# iot1.net
KiCad netlist of a schematic drawn in EAGLE
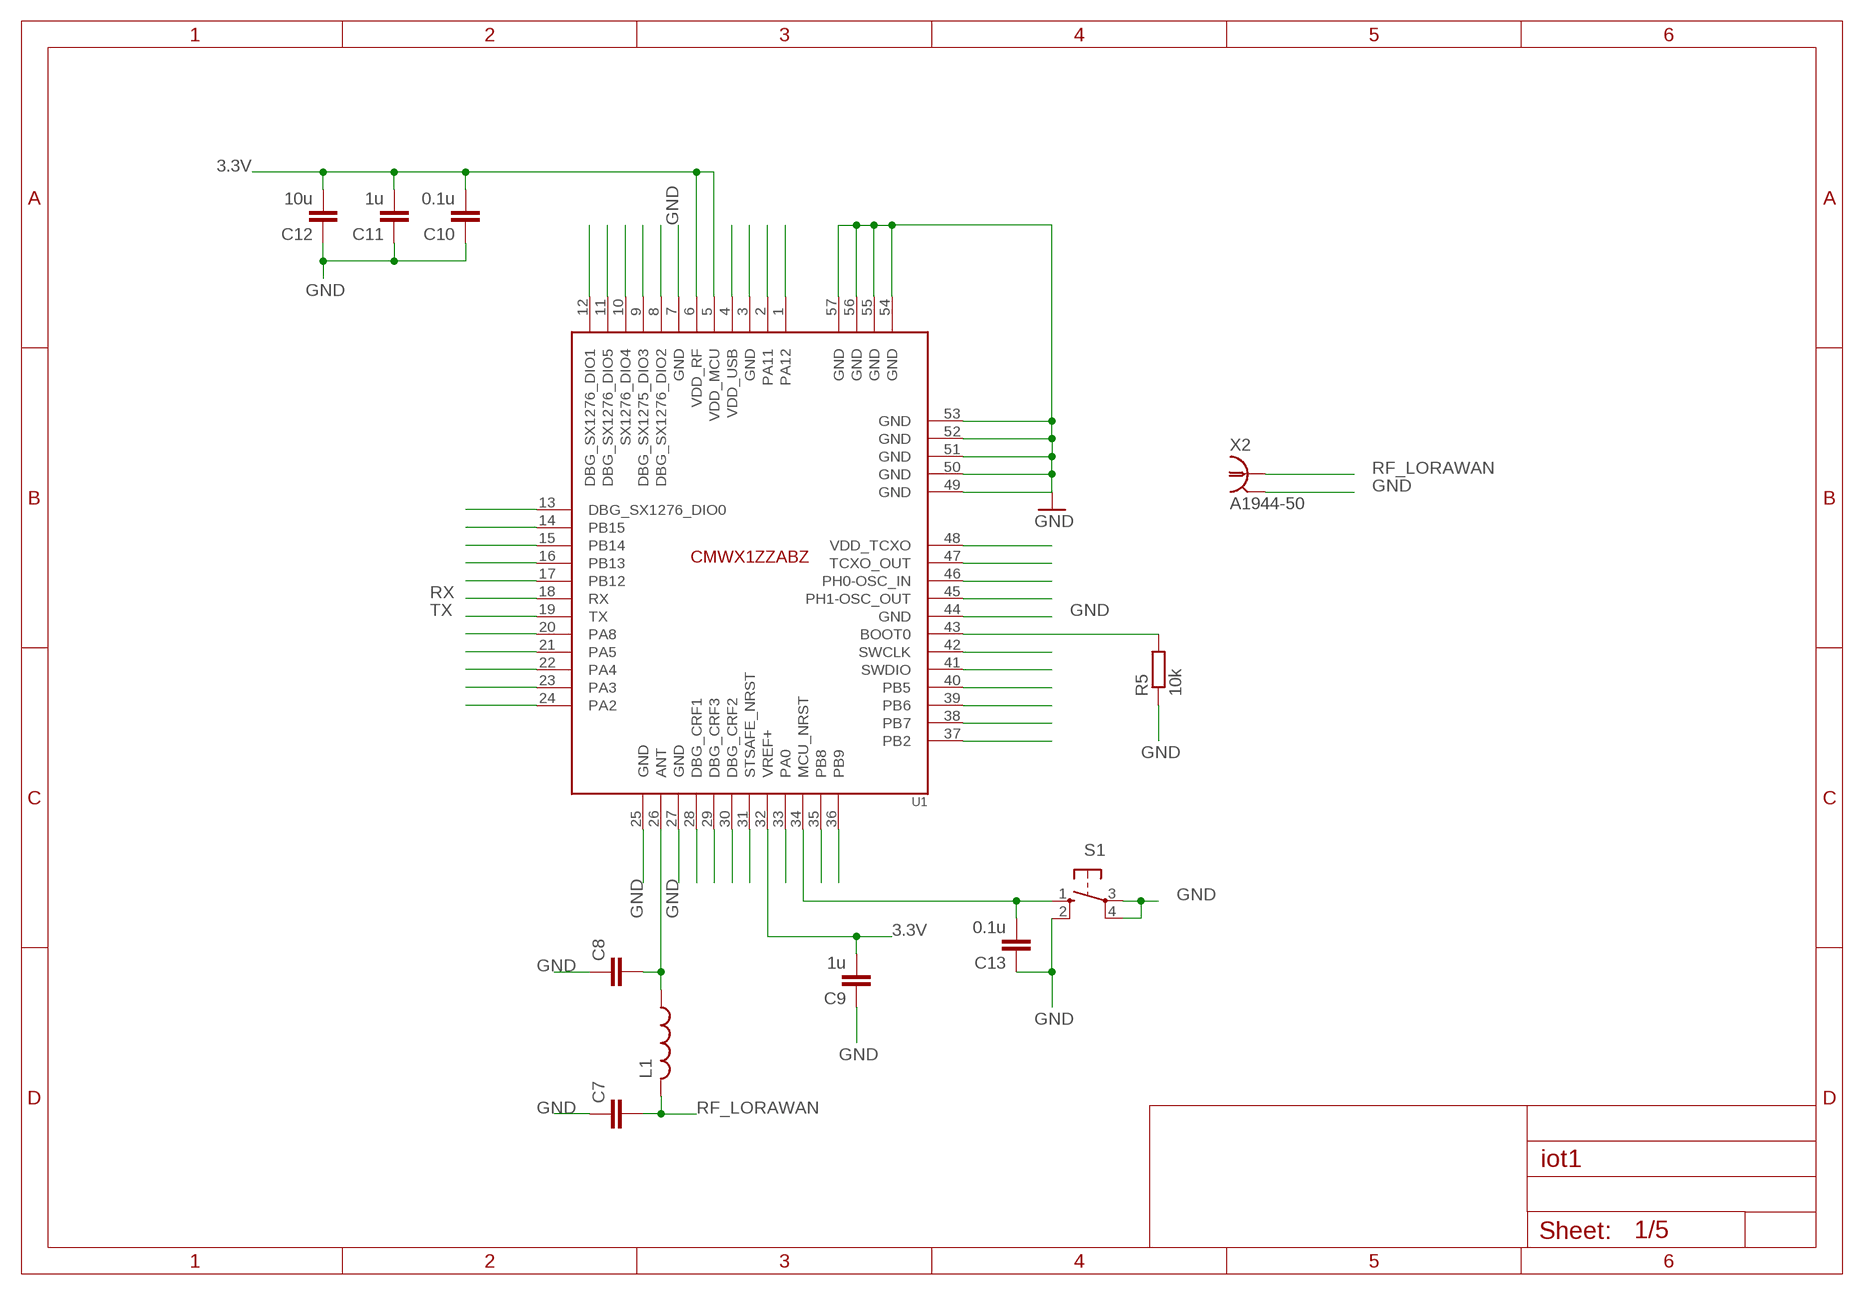
[diagram p0: schematic, sheet 1]
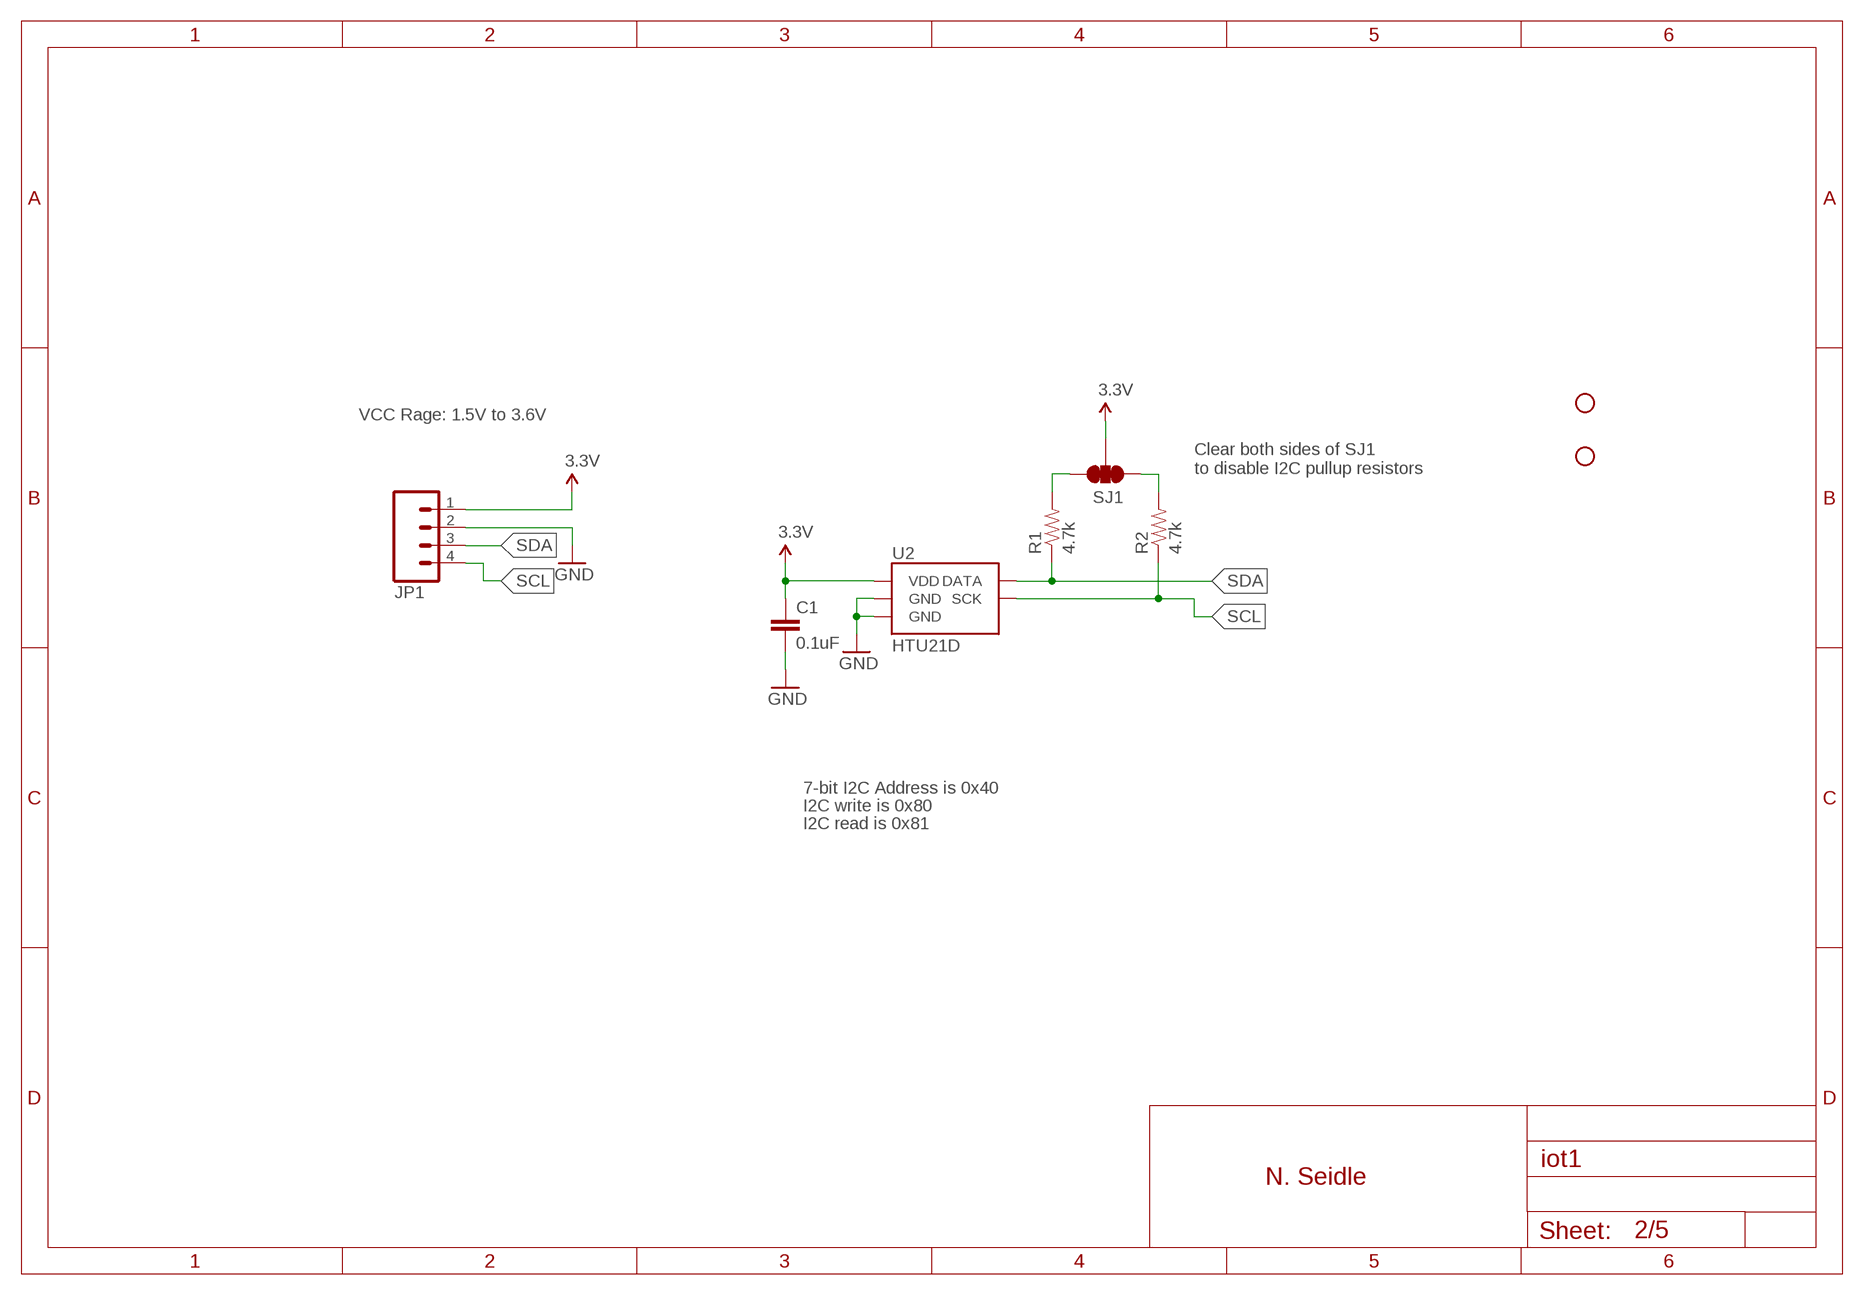
[diagram p1: schematic, sheet 2]
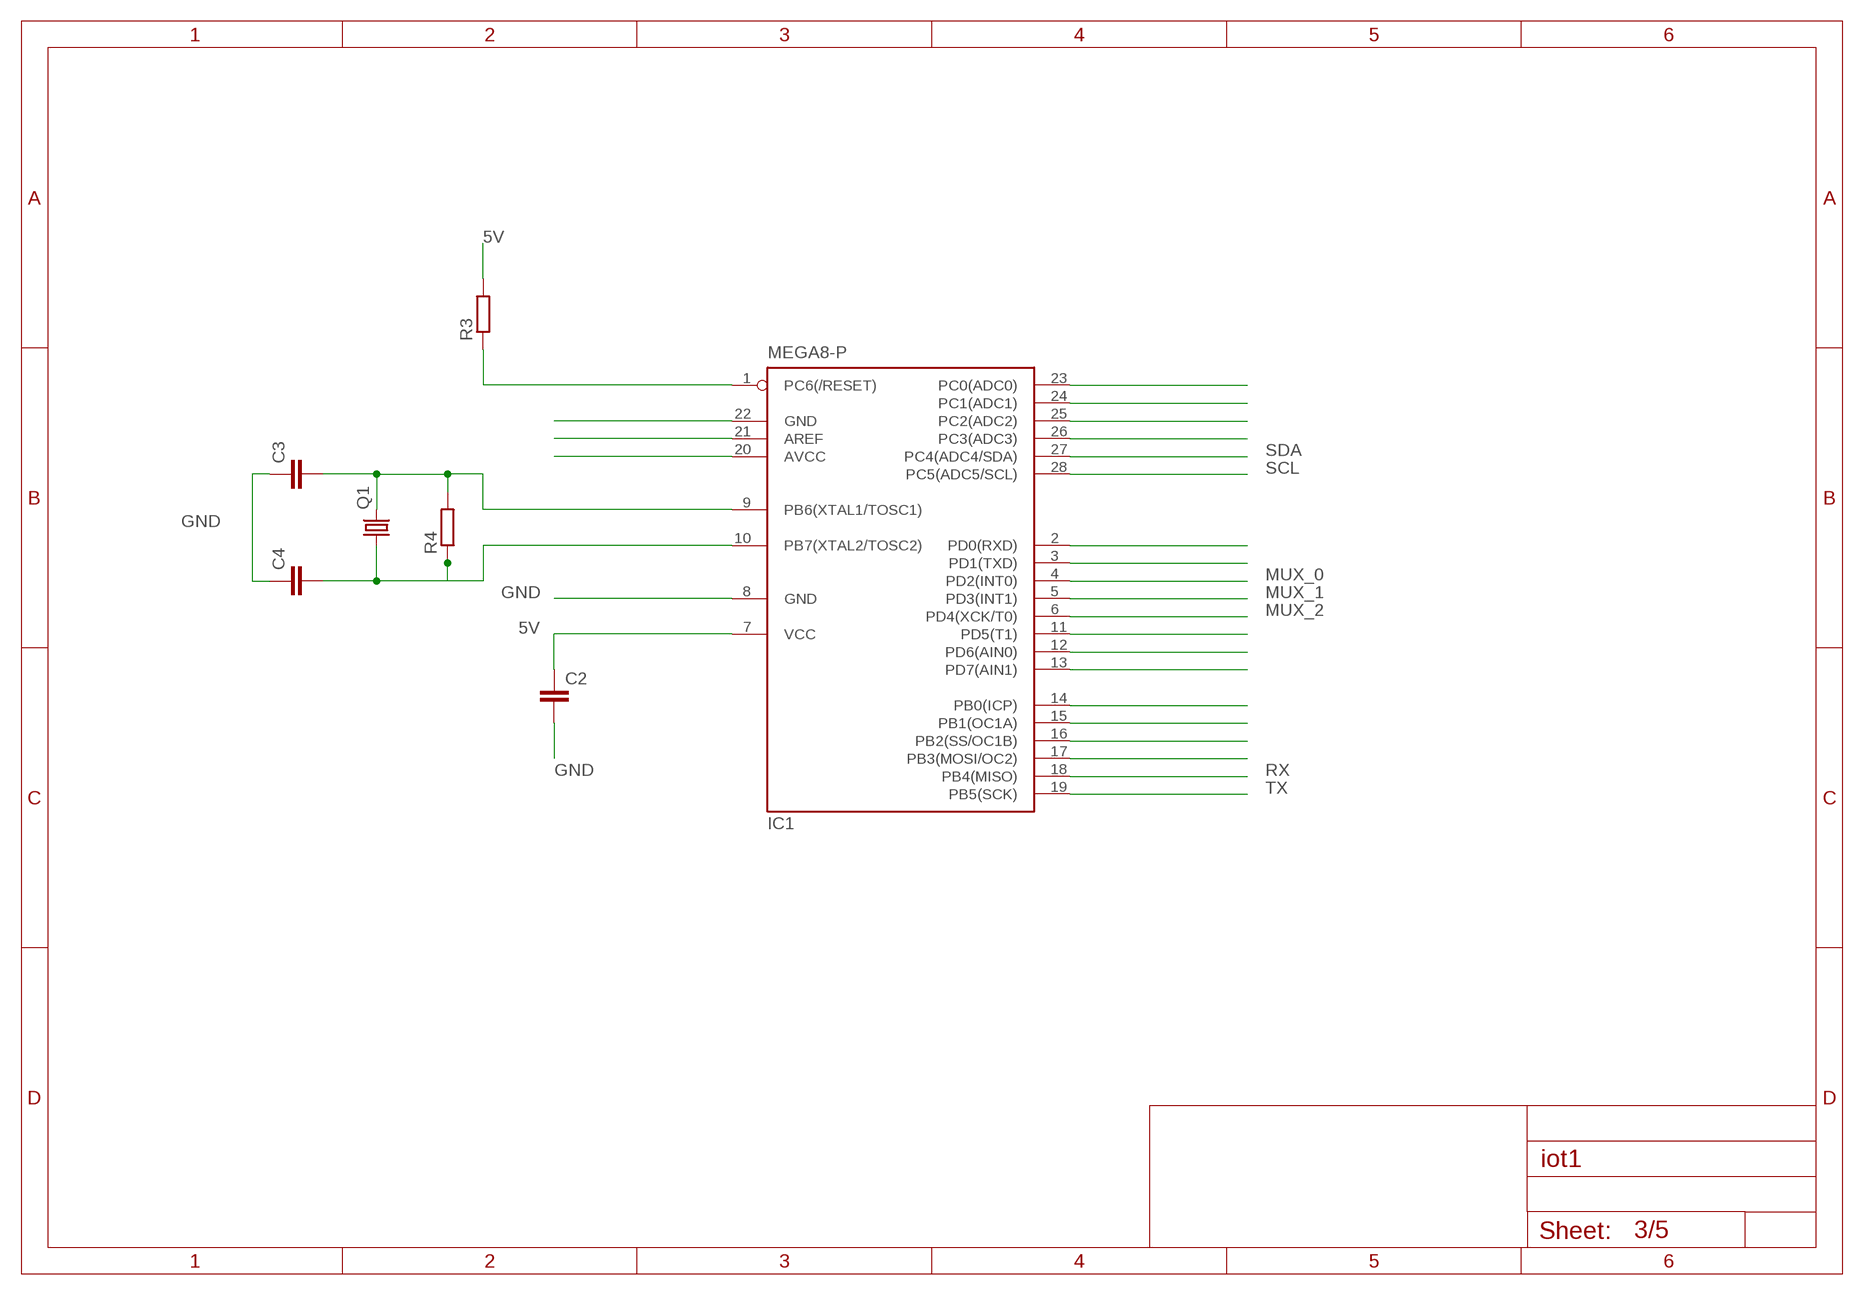
[diagram p2: schematic, sheet 3]
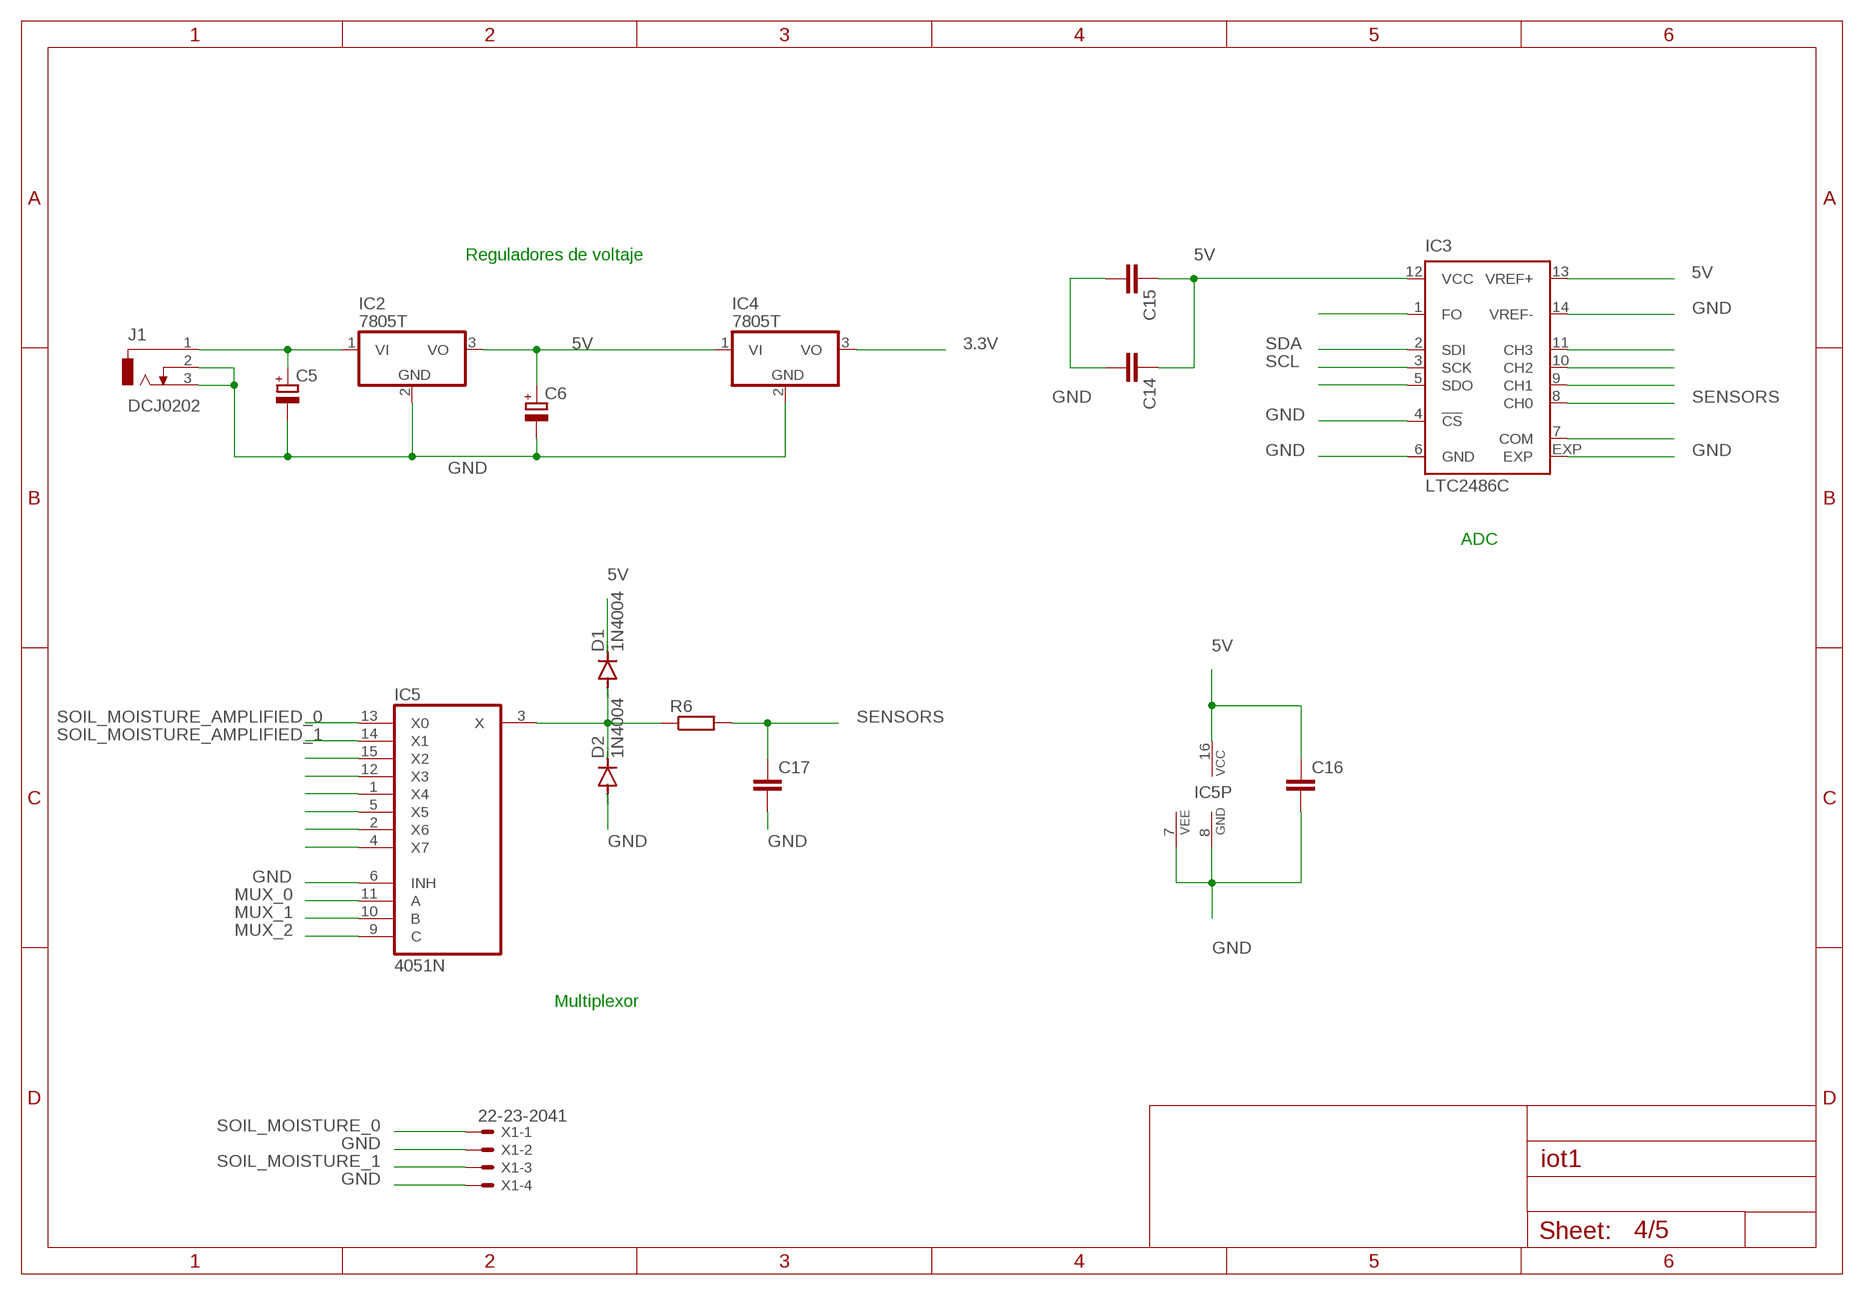
[diagram p3: schematic, sheet 4]
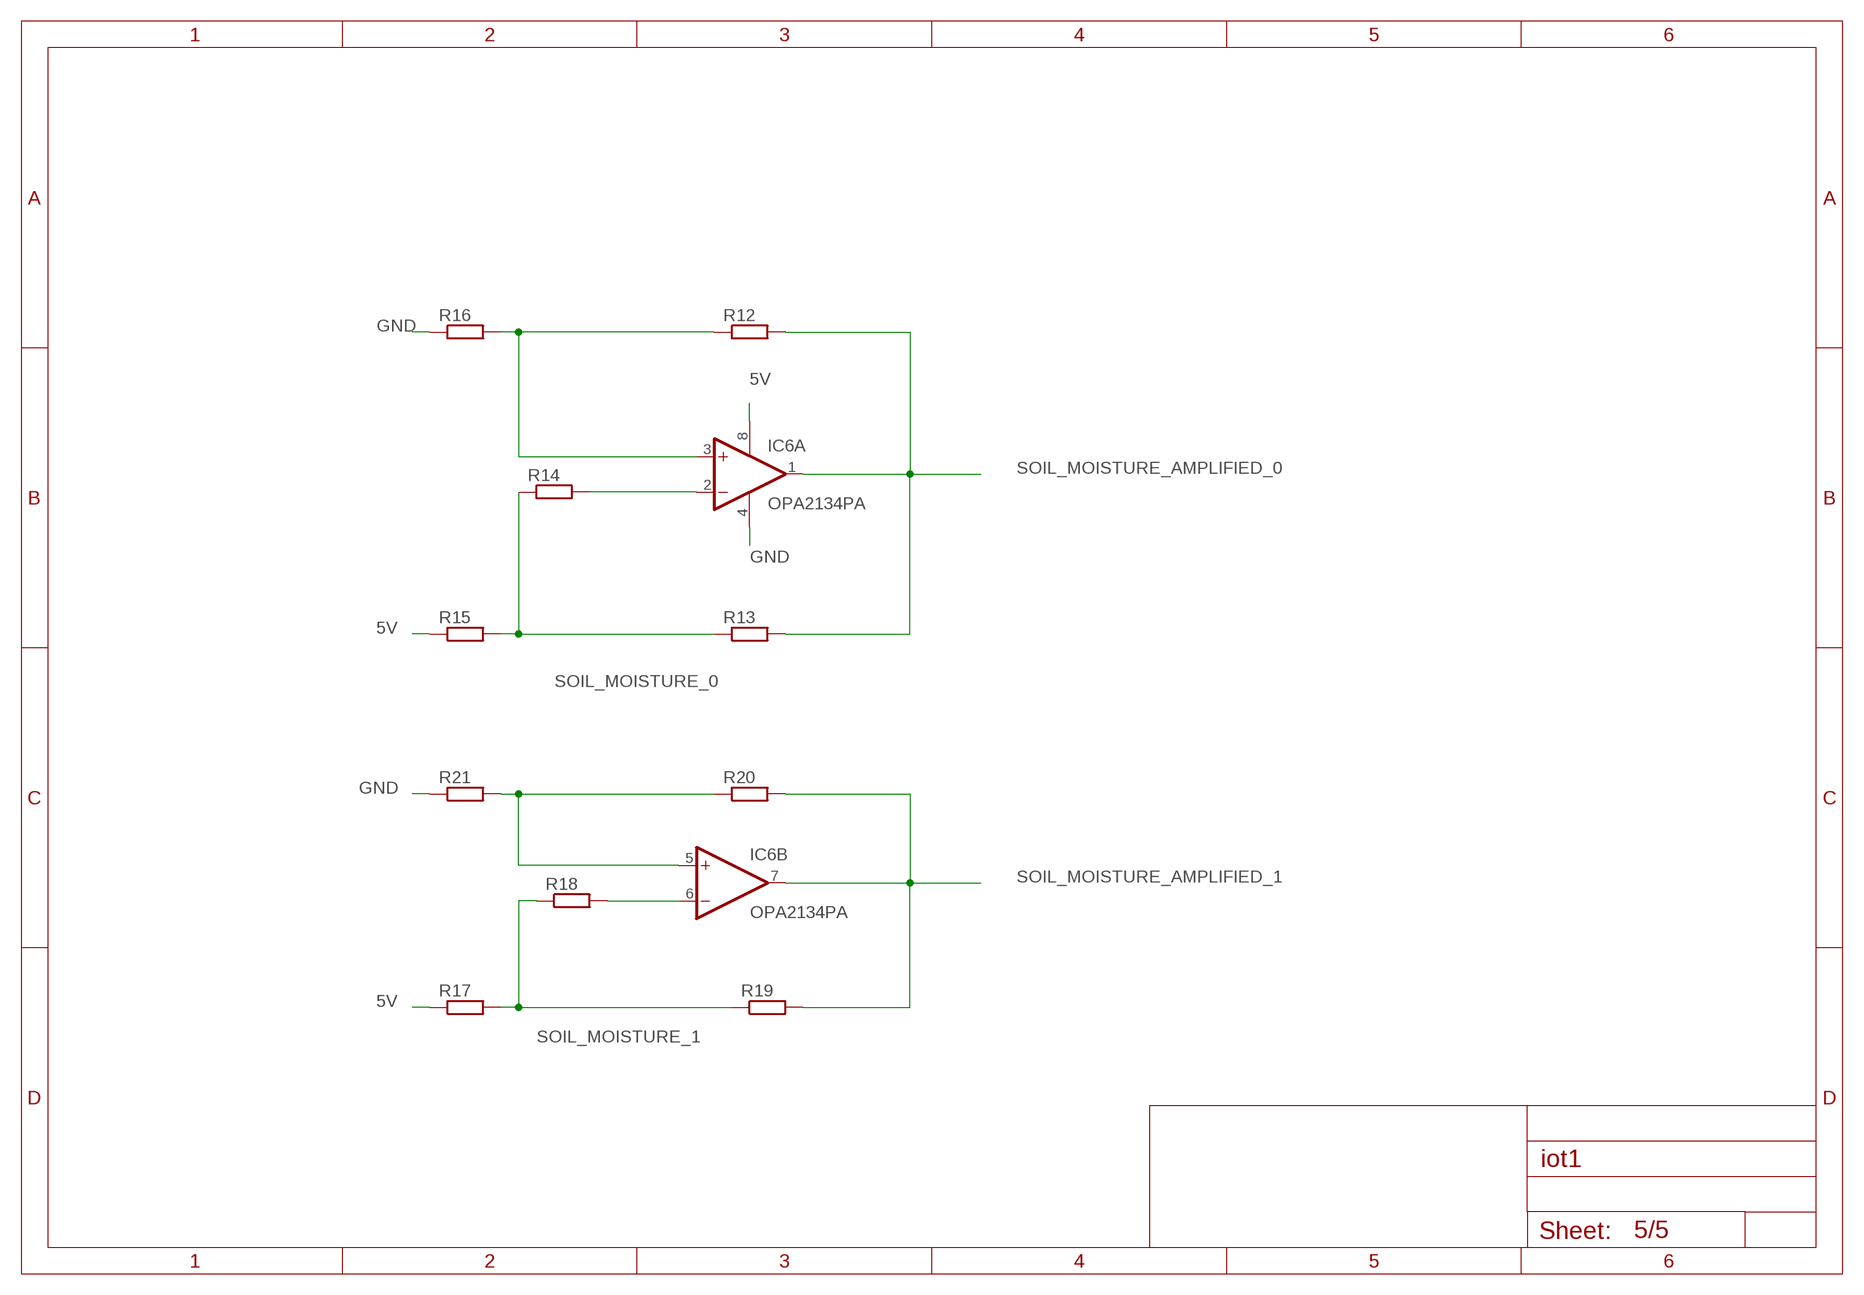
[diagram p4: schematic, sheet 5]

(export (version "E")
  (design (tool "Eeschema 10.0.6"))
  (components
    (comp (ref "C7")
      (value "C-EU050-025X075")
      (footprint "eagle-import:C050-025X075")
      (libsource (lib "eagle-import") (part "C-EU050-025X075"))
    )
    (comp (ref "C8")
      (value "C-EU050-025X075")
      (footprint "eagle-import:C050-025X075")
      (libsource (lib "eagle-import") (part "C-EU050-025X075"))
    )
    (comp (ref "C9")
      (value "1u")
      (footprint "eagle-import:C050-025X075")
      (libsource (lib "eagle-import") (part "C-EU050-025X075"))
    )
    (comp (ref "C10")
      (value "0.1u")
      (footprint "eagle-import:C050-025X075")
      (libsource (lib "eagle-import") (part "C-EU050-025X075"))
    )
    (comp (ref "C11")
      (value "1u")
      (footprint "eagle-import:C050-025X075")
      (libsource (lib "eagle-import") (part "C-EU050-025X075"))
    )
    (comp (ref "C12")
      (value "10u")
      (footprint "eagle-import:C050-025X075")
      (libsource (lib "eagle-import") (part "C-EU050-025X075"))
    )
    (comp (ref "C13")
      (value "0.1u")
      (footprint "eagle-import:C050-025X075")
      (libsource (lib "eagle-import") (part "C-EU050-025X075"))
    )
    (comp (ref "L1")
      (value "L-US0207/7")
      (footprint "eagle-import:0207_7")
      (libsource (lib "eagle-import") (part "L-US0207/7"))
    )
    (comp (ref "R5")
      (value "10k")
      (footprint "eagle-import:0204_5")
      (libsource (lib "eagle-import") (part "R-EU_0204/5"))
    )
    (comp (ref "S1")
      (value "10-XX")
      (footprint "eagle-import:B3F-10XX")
      (fields (field (name "MPN") "B3F-1000"))
      (libsource (lib "eagle-import") (part "10-XX"))
    )
    (comp (ref "U1")
      (value "CMWX1ZZABZ")
      (footprint "eagle-import:CMWX1ZZABZ")
      (libsource (lib "eagle-import") (part "CMWX1ZZABZ"))
    )
    (comp (ref "X2")
      (value "A1944-50")
      (footprint "eagle-import:A1944")
      (libsource (lib "eagle-import") (part "A1944-50"))
    )
    (comp (ref "C2")
      (value "C-EU050-025X075")
      (footprint "eagle-import:C050-025X075")
      (libsource (lib "eagle-import") (part "C-EU050-025X075"))
    )
    (comp (ref "C3")
      (value "C-EU050-025X075")
      (footprint "eagle-import:C050-025X075")
      (libsource (lib "eagle-import") (part "C-EU050-025X075"))
    )
    (comp (ref "C4")
      (value "C-EU050-025X075")
      (footprint "eagle-import:C050-025X075")
      (libsource (lib "eagle-import") (part "C-EU050-025X075"))
    )
    (comp (ref "IC1")
      (value "MEGA8-P")
      (footprint "eagle-import:DIL28-3")
      (libsource (lib "eagle-import") (part "MEGA8-P"))
    )
    (comp (ref "Q1")
      (value "CRYSTALHC18U-V")
      (footprint "eagle-import:HC18U-V")
      (libsource (lib "eagle-import") (part "CRYSTALHC18U-V"))
    )
    (comp (ref "R3")
      (value "R-EU_0204/7")
      (footprint "eagle-import:0204_7")
      (libsource (lib "eagle-import") (part "R-EU_0204/7"))
    )
    (comp (ref "R4")
      (value "R-EU_0204/7")
      (footprint "eagle-import:0204_7")
      (libsource (lib "eagle-import") (part "R-EU_0204/7"))
    )
    (comp (ref "C1")
      (value "0.1uF")
      (footprint "eagle-import:0603-CAP")
      (libsource (lib "eagle-import") (part "CAP0603-CAP"))
    )
    (comp (ref "JP1")
      (value "M04PTH")
      (footprint "eagle-import:1X04")
      (libsource (lib "eagle-import") (part "M04PTH"))
    )
    (comp (ref "R1")
      (value "4.7k")
      (footprint "eagle-import:0603-RES")
      (libsource (lib "eagle-import") (part "RESISTOR0603-RES"))
    )
    (comp (ref "R2")
      (value "4.7k")
      (footprint "eagle-import:0603-RES")
      (libsource (lib "eagle-import") (part "RESISTOR0603-RES"))
    )
    (comp (ref "SJ1")
      (value "SOLDERJUMPER_2WAYPASTE1&2&3")
      (footprint "eagle-import:SJ_3_PASTE1&2&3")
      (libsource (lib "eagle-import") (part "SOLDERJUMPER_2WAYPASTE1&2&3"))
    )
    (comp (ref "STANDOFF1")
      (value "STAND-OFF")
      (footprint "eagle-import:STAND-OFF")
      (libsource (lib "eagle-import") (part "STAND-OFF"))
    )
    (comp (ref "STANDOFF2")
      (value "STAND-OFF")
      (footprint "eagle-import:STAND-OFF")
      (libsource (lib "eagle-import") (part "STAND-OFF"))
    )
    (comp (ref "U2")
      (value "HTU21D")
      (footprint "eagle-import:HTU21D")
      (libsource (lib "eagle-import") (part "HTU21DSMD"))
    )
    (comp (ref "IC6")
      (value "OPA2134PA")
      (footprint "eagle-import:DIL08")
      (libsource (lib "eagle-import") (part "OPA2PA134"))
    )
    (comp (ref "R12")
      (value "R-EU_0207/10")
      (footprint "eagle-import:0207_10")
      (libsource (lib "eagle-import") (part "R-EU_0207/10"))
    )
    (comp (ref "R13")
      (value "R-EU_0207/10")
      (footprint "eagle-import:0207_10")
      (libsource (lib "eagle-import") (part "R-EU_0207/10"))
    )
    (comp (ref "R14")
      (value "R-EU_0207/10")
      (footprint "eagle-import:0207_10")
      (libsource (lib "eagle-import") (part "R-EU_0207/10"))
    )
    (comp (ref "R15")
      (value "R-EU_0207/10")
      (footprint "eagle-import:0207_10")
      (libsource (lib "eagle-import") (part "R-EU_0207/10"))
    )
    (comp (ref "R16")
      (value "R-EU_0207/10")
      (footprint "eagle-import:0207_10")
      (libsource (lib "eagle-import") (part "R-EU_0207/10"))
    )
    (comp (ref "R17")
      (value "R-EU_0207/10")
      (footprint "eagle-import:0207_10")
      (libsource (lib "eagle-import") (part "R-EU_0207/10"))
    )
    (comp (ref "R18")
      (value "R-EU_0207/10")
      (footprint "eagle-import:0207_10")
      (libsource (lib "eagle-import") (part "R-EU_0207/10"))
    )
    (comp (ref "R19")
      (value "R-EU_0207/10")
      (footprint "eagle-import:0207_10")
      (libsource (lib "eagle-import") (part "R-EU_0207/10"))
    )
    (comp (ref "R20")
      (value "R-EU_0207/10")
      (footprint "eagle-import:0207_10")
      (libsource (lib "eagle-import") (part "R-EU_0207/10"))
    )
    (comp (ref "R21")
      (value "R-EU_0207/10")
      (footprint "eagle-import:0207_10")
      (libsource (lib "eagle-import") (part "R-EU_0207/10"))
    )
    (comp (ref "C5")
      (value "CPOL-EUE1.8-4")
      (footprint "eagle-import:E1,8-4")
      (libsource (lib "eagle-import") (part "CPOL-EUE1.8-4"))
    )
    (comp (ref "C6")
      (value "CPOL-EUE1.8-4")
      (footprint "eagle-import:E1,8-4")
      (libsource (lib "eagle-import") (part "CPOL-EUE1.8-4"))
    )
    (comp (ref "C14")
      (value "C-EUC0603")
      (footprint "eagle-import:C0603")
      (libsource (lib "eagle-import") (part "C-EUC0603"))
    )
    (comp (ref "C15")
      (value "C-EUC0603")
      (footprint "eagle-import:C0603")
      (libsource (lib "eagle-import") (part "C-EUC0603"))
    )
    (comp (ref "C16")
      (value "C-EUC0603")
      (footprint "eagle-import:C0603")
      (libsource (lib "eagle-import") (part "C-EUC0603"))
    )
    (comp (ref "C17")
      (value "C-EUC0603")
      (footprint "eagle-import:C0603")
      (libsource (lib "eagle-import") (part "C-EUC0603"))
    )
    (comp (ref "D1")
      (value "1N4004")
      (footprint "eagle-import:DO41-10")
      (libsource (lib "eagle-import") (part "1N4004"))
    )
    (comp (ref "D2")
      (value "1N4004")
      (footprint "eagle-import:DO41-10")
      (libsource (lib "eagle-import") (part "1N4004"))
    )
    (comp (ref "IC2")
      (value "7805T")
      (footprint "eagle-import:TO220H")
      (libsource (lib "eagle-import") (part "78T05"))
    )
    (comp (ref "IC3")
      (value "LTC2486C")
      (footprint "eagle-import:DFN14-4X3")
      (libsource (lib "eagle-import") (part "LTC2486C"))
    )
    (comp (ref "IC4")
      (value "7805T")
      (footprint "eagle-import:TO220H")
      (libsource (lib "eagle-import") (part "78T05"))
    )
    (comp (ref "IC5")
      (value "4051N")
      (footprint "eagle-import:DIL16")
      (libsource (lib "eagle-import") (part "4051N"))
    )
    (comp (ref "J1")
      (value "DCJ0202")
      (footprint "eagle-import:DCJ0202")
      (libsource (lib "eagle-import") (part "DCJ0202"))
    )
    (comp (ref "R6")
      (value "R-EU_0207/10")
      (footprint "eagle-import:0207_10")
      (libsource (lib "eagle-import") (part "R-EU_0207/10"))
    )
    (comp (ref "X1")
      (value "22-23-2041")
      (footprint "eagle-import:22-23-2041")
      (fields (field (name "MF") "MOLEX"))
      (libsource (lib "eagle-import") (part "22-23-2041"))
    )
  )
  (nets
    (net (code "1") (name "3.3V") (class "Default")
      (node (ref "C1") (pin "1") (pinfunction "1_1") (pintype "passive"))
      (node (ref "C10") (pin "2") (pinfunction "2_2") (pintype "passive"))
      (node (ref "C11") (pin "2") (pinfunction "2_2") (pintype "passive"))
      (node (ref "C12") (pin "2") (pinfunction "2_2") (pintype "passive"))
      (node (ref "C9") (pin "2") (pinfunction "2_2") (pintype "passive"))
      (node (ref "IC4") (pin "3") (pinfunction "VO_3") (pintype "passive"))
      (node (ref "JP1") (pin "1") (pinfunction "1_1") (pintype "passive"))
      (node (ref "SJ1") (pin "2") (pinfunction "2_2") (pintype "passive"))
      (node (ref "U1") (pin "32") (pinfunction "VREF+_32") (pintype "bidirectional"))
      (node (ref "U1") (pin "5") (pinfunction "VDD_MCU_5") (pintype "bidirectional"))
      (node (ref "U1") (pin "6") (pinfunction "VDD_RF_6") (pintype "bidirectional"))
      (node (ref "U2") (pin "VDD") (pinfunction "VDD_VDD") (pintype "power_in"))
    )
    (net (code "2") (name "5V") (class "Default")
      (node (ref "C14") (pin "1") (pinfunction "1_1") (pintype "passive"))
      (node (ref "C15") (pin "1") (pinfunction "1_1") (pintype "passive"))
      (node (ref "C16") (pin "1") (pinfunction "1_1") (pintype "passive"))
      (node (ref "C2") (pin "1") (pinfunction "1_1") (pintype "passive"))
      (node (ref "C6") (pin "+") (pinfunction "+_+") (pintype "passive"))
      (node (ref "D1") (pin "C") (pinfunction "C_C") (pintype "passive"))
      (node (ref "IC1") (pin "7") (pinfunction "VCC_7") (pintype "power_in"))
      (node (ref "IC2") (pin "3") (pinfunction "VO_3") (pintype "passive"))
      (node (ref "IC3") (pin "12") (pinfunction "VCC_12") (pintype "power_in"))
      (node (ref "IC3") (pin "13") (pinfunction "VREF+_13") (pintype "input"))
      (node (ref "IC4") (pin "1") (pinfunction "VI_1") (pintype "input"))
      (node (ref "IC5") (pin "16") (pinfunction "VCC_16") (pintype "power_in"))
      (node (ref "IC6") (pin "8") (pinfunction "V+_8") (pintype "power_in"))
      (node (ref "R15") (pin "1") (pinfunction "1_1") (pintype "passive"))
      (node (ref "R17") (pin "1") (pinfunction "1_1") (pintype "passive"))
      (node (ref "R3") (pin "2") (pinfunction "2_2") (pintype "passive"))
    )
    (net (code "3") (name "GND") (class "Default")
      (node (ref "C1") (pin "2") (pinfunction "2_2") (pintype "passive"))
      (node (ref "C10") (pin "1") (pinfunction "1_1") (pintype "passive"))
      (node (ref "C11") (pin "1") (pinfunction "1_1") (pintype "passive"))
      (node (ref "C12") (pin "1") (pinfunction "1_1") (pintype "passive"))
      (node (ref "C13") (pin "1") (pinfunction "1_1") (pintype "passive"))
      (node (ref "C14") (pin "2") (pinfunction "2_2") (pintype "passive"))
      (node (ref "C15") (pin "2") (pinfunction "2_2") (pintype "passive"))
      (node (ref "C16") (pin "2") (pinfunction "2_2") (pintype "passive"))
      (node (ref "C17") (pin "2") (pinfunction "2_2") (pintype "passive"))
      (node (ref "C2") (pin "2") (pinfunction "2_2") (pintype "passive"))
      (node (ref "C3") (pin "1") (pinfunction "1_1") (pintype "passive"))
      (node (ref "C4") (pin "1") (pinfunction "1_1") (pintype "passive"))
      (node (ref "C5") (pin "-") (pinfunction "-_-") (pintype "passive"))
      (node (ref "C6") (pin "-") (pinfunction "-_-") (pintype "passive"))
      (node (ref "C7") (pin "1") (pinfunction "1_1") (pintype "passive"))
      (node (ref "C8") (pin "1") (pinfunction "1_1") (pintype "passive"))
      (node (ref "C9") (pin "1") (pinfunction "1_1") (pintype "passive"))
      (node (ref "D2") (pin "A") (pinfunction "A_A") (pintype "passive"))
      (node (ref "IC1") (pin "8") (pinfunction "GND_8") (pintype "power_in"))
      (node (ref "IC2") (pin "2") (pinfunction "GND_2") (pintype "passive"))
      (node (ref "IC3") (pin "14") (pinfunction "VREF-_14") (pintype "input"))
      (node (ref "IC3") (pin "4") (pinfunction "~{CS}_4") (pintype "input"))
      (node (ref "IC3") (pin "6") (pinfunction "GND_6") (pintype "power_in"))
      (node (ref "IC3") (pin "EXP") (pinfunction "EXP_EXP") (pintype "input"))
      (node (ref "IC4") (pin "2") (pinfunction "GND_2") (pintype "passive"))
      (node (ref "IC5") (pin "6") (pinfunction "INH_6") (pintype "input"))
      (node (ref "IC5") (pin "7") (pinfunction "VEE_7") (pintype "power_in"))
      (node (ref "IC5") (pin "8") (pinfunction "GND_8") (pintype "power_in"))
      (node (ref "IC6") (pin "4") (pinfunction "V-_4") (pintype "power_in"))
      (node (ref "J1") (pin "2") (pinfunction "2_2") (pintype "passive"))
      (node (ref "J1") (pin "3") (pinfunction "3_3") (pintype "passive"))
      (node (ref "JP1") (pin "2") (pinfunction "2_2") (pintype "passive"))
      (node (ref "R16") (pin "1") (pinfunction "1_1") (pintype "passive"))
      (node (ref "R21") (pin "1") (pinfunction "1_1") (pintype "passive"))
      (node (ref "R5") (pin "1") (pinfunction "1_1") (pintype "passive"))
      (node (ref "S1") (pin "2") (pinfunction "S1_2") (pintype "passive"))
      (node (ref "S1") (pin "3") (pinfunction "P_3") (pintype "passive"))
      (node (ref "S1") (pin "4") (pinfunction "P1_4") (pintype "passive"))
      (node (ref "U1") (pin "25") (pinfunction "GND_25") (pintype "bidirectional"))
      (node (ref "U1") (pin "27") (pinfunction "GND_27") (pintype "bidirectional"))
      (node (ref "U1") (pin "44") (pinfunction "GND_44") (pintype "bidirectional"))
      (node (ref "U1") (pin "49") (pinfunction "GND_49") (pintype "bidirectional"))
      (node (ref "U1") (pin "50") (pinfunction "GND_50") (pintype "bidirectional"))
      (node (ref "U1") (pin "51") (pinfunction "GND_51") (pintype "bidirectional"))
      (node (ref "U1") (pin "52") (pinfunction "GND_52") (pintype "bidirectional"))
      (node (ref "U1") (pin "53") (pinfunction "GND_53") (pintype "bidirectional"))
      (node (ref "U1") (pin "54") (pinfunction "GND_54") (pintype "bidirectional"))
      (node (ref "U1") (pin "55") (pinfunction "GND_55") (pintype "bidirectional"))
      (node (ref "U1") (pin "56") (pinfunction "GND_56") (pintype "bidirectional"))
      (node (ref "U1") (pin "57") (pinfunction "GND_57") (pintype "bidirectional"))
      (node (ref "U1") (pin "7") (pinfunction "GND_7") (pintype "bidirectional"))
      (node (ref "U2") (pin "7") (pinfunction "GND_7") (pintype "power_in"))
      (node (ref "U2") (pin "GND") (pinfunction "GND_GND") (pintype "power_in"))
      (node (ref "X1") (pin "2") (pinfunction "S_2") (pintype "passive"))
      (node (ref "X1") (pin "4") (pinfunction "S_4") (pintype "passive"))
      (node (ref "X2") (pin "2") (pinfunction "2_2") (pintype "passive"))
      (node (ref "X2") (pin "3") (pinfunction "2_3") (pintype "passive"))
      (node (ref "X2") (pin "4") (pinfunction "2_4") (pintype "passive"))
      (node (ref "X2") (pin "5") (pinfunction "2_5") (pintype "passive"))
    )
    (net (code "4") (name "MUX_0") (class "Default")
      (node (ref "IC1") (pin "4") (pinfunction "PD2(INT0)_4") (pintype "bidirectional"))
      (node (ref "IC5") (pin "11") (pinfunction "A_11") (pintype "input"))
    )
    (net (code "5") (name "MUX_1") (class "Default")
      (node (ref "IC1") (pin "5") (pinfunction "PD3(INT1)_5") (pintype "bidirectional"))
      (node (ref "IC5") (pin "10") (pinfunction "B_10") (pintype "input"))
    )
    (net (code "6") (name "MUX_2") (class "Default")
      (node (ref "IC1") (pin "6") (pinfunction "PD4(XCK/T0)_6") (pintype "bidirectional"))
      (node (ref "IC5") (pin "9") (pinfunction "C_9") (pintype "input"))
    )
    (net (code "7") (name "Net-(IC1-PB6(XTAL1{slash}TOSC1))") (class "Default")
      (node (ref "C3") (pin "2") (pinfunction "2_2") (pintype "passive"))
      (node (ref "IC1") (pin "9") (pinfunction "PB6(XTAL1/TOSC1)_9") (pintype "bidirectional"))
      (node (ref "Q1") (pin "2") (pinfunction "2_2") (pintype "passive"))
      (node (ref "R4") (pin "2") (pinfunction "2_2") (pintype "passive"))
    )
    (net (code "8") (name "Net-(IC1-PB7(XTAL2{slash}TOSC2))") (class "Default")
      (node (ref "C4") (pin "2") (pinfunction "2_2") (pintype "passive"))
      (node (ref "IC1") (pin "10") (pinfunction "PB7(XTAL2/TOSC2)_10") (pintype "bidirectional"))
      (node (ref "Q1") (pin "1") (pinfunction "1_1") (pintype "passive"))
      (node (ref "R4") (pin "1") (pinfunction "1_1") (pintype "passive"))
    )
    (net (code "9") (name "Net-(IC1-PC6({slash}RESET))") (class "Default")
      (node (ref "IC1") (pin "1") (pinfunction "PC6(/RESET)_1") (pintype "bidirectional"))
      (node (ref "R3") (pin "1") (pinfunction "1_1") (pintype "passive"))
    )
    (net (code "10") (name "Net-(IC2-VI)") (class "Default")
      (node (ref "C5") (pin "+") (pinfunction "+_+") (pintype "passive"))
      (node (ref "IC2") (pin "1") (pinfunction "VI_1") (pintype "input"))
      (node (ref "J1") (pin "1") (pinfunction "1_1") (pintype "passive"))
    )
    (net (code "11") (name "Net-(IC5A-X)") (class "Default")
      (node (ref "D1") (pin "A") (pinfunction "A_A") (pintype "passive"))
      (node (ref "D2") (pin "C") (pinfunction "C_C") (pintype "passive"))
      (node (ref "IC5") (pin "3") (pinfunction "X_3") (pintype "bidirectional"))
      (node (ref "R6") (pin "1") (pinfunction "1_1") (pintype "passive"))
    )
    (net (code "12") (name "Net-(IC6A-+IN)") (class "Default")
      (node (ref "IC6") (pin "3") (pinfunction "+IN_3") (pintype "input"))
      (node (ref "R12") (pin "1") (pinfunction "1_1") (pintype "passive"))
      (node (ref "R16") (pin "2") (pinfunction "2_2") (pintype "passive"))
    )
    (net (code "13") (name "Net-(IC6A--IN)") (class "Default")
      (node (ref "IC6") (pin "2") (pinfunction "-IN_2") (pintype "input"))
      (node (ref "R14") (pin "2") (pinfunction "2_2") (pintype "passive"))
    )
    (net (code "14") (name "Net-(IC6B-+IN)") (class "Default")
      (node (ref "IC6") (pin "5") (pinfunction "+IN_5") (pintype "input"))
      (node (ref "R20") (pin "1") (pinfunction "1_1") (pintype "passive"))
      (node (ref "R21") (pin "2") (pinfunction "2_2") (pintype "passive"))
    )
    (net (code "15") (name "Net-(IC6B--IN)") (class "Default")
      (node (ref "IC6") (pin "6") (pinfunction "-IN_6") (pintype "input"))
      (node (ref "R18") (pin "2") (pinfunction "2_2") (pintype "passive"))
    )
    (net (code "16") (name "Net-(R1-Pad2)") (class "Default")
      (node (ref "R1") (pin "2") (pinfunction "2_2") (pintype "passive"))
      (node (ref "SJ1") (pin "3") (pinfunction "3_3") (pintype "passive"))
    )
    (net (code "17") (name "Net-(R2-Pad2)") (class "Default")
      (node (ref "R2") (pin "2") (pinfunction "2_2") (pintype "passive"))
      (node (ref "SJ1") (pin "1") (pinfunction "1_1") (pintype "passive"))
    )
    (net (code "18") (name "Net-(S1-S)") (class "Default")
      (node (ref "C13") (pin "2") (pinfunction "2_2") (pintype "passive"))
      (node (ref "S1") (pin "1") (pinfunction "S_1") (pintype "passive"))
      (node (ref "U1") (pin "34") (pinfunction "MCU_NRST_34") (pintype "bidirectional"))
    )
    (net (code "19") (name "Net-(U1-ANT)") (class "Default")
      (node (ref "C8") (pin "2") (pinfunction "2_2") (pintype "passive"))
      (node (ref "L1") (pin "1") (pinfunction "1_1") (pintype "passive"))
      (node (ref "U1") (pin "26") (pinfunction "ANT_26") (pintype "bidirectional"))
    )
    (net (code "20") (name "Net-(U1-BOOT0)") (class "Default")
      (node (ref "R5") (pin "2") (pinfunction "2_2") (pintype "passive"))
      (node (ref "U1") (pin "43") (pinfunction "BOOT0_43") (pintype "bidirectional"))
    )
    (net (code "21") (name "RF_LORAWAN") (class "Default")
      (node (ref "C7") (pin "2") (pinfunction "2_2") (pintype "passive"))
      (node (ref "L1") (pin "2") (pinfunction "2_2") (pintype "passive"))
      (node (ref "X2") (pin "1") (pinfunction "1_1") (pintype "passive"))
    )
    (net (code "22") (name "RX") (class "Default")
      (node (ref "IC1") (pin "18") (pinfunction "PB4(MISO)_18") (pintype "bidirectional"))
      (node (ref "U1") (pin "18") (pinfunction "RX_18") (pintype "bidirectional"))
    )
    (net (code "23") (name "SCL") (class "Default")
      (node (ref "IC1") (pin "28") (pinfunction "PC5(ADC5/SCL)_28") (pintype "bidirectional"))
      (node (ref "IC3") (pin "1") (pinfunction "FO_1") (pintype "input"))
      (node (ref "IC3") (pin "3") (pinfunction "SCK_3") (pintype "input"))
      (node (ref "JP1") (pin "4") (pinfunction "4_4") (pintype "passive"))
      (node (ref "R2") (pin "1") (pinfunction "1_1") (pintype "passive"))
      (node (ref "U2") (pin "SCK") (pinfunction "SCK_SCK") (pintype "input"))
    )
    (net (code "24") (name "SDA") (class "Default")
      (node (ref "IC1") (pin "27") (pinfunction "PC4(ADC4/SDA)_27") (pintype "bidirectional"))
      (node (ref "IC3") (pin "2") (pinfunction "SDI_2") (pintype "input"))
      (node (ref "JP1") (pin "3") (pinfunction "3_3") (pintype "passive"))
      (node (ref "R1") (pin "1") (pinfunction "1_1") (pintype "passive"))
      (node (ref "U2") (pin "DATA") (pinfunction "DATA_DATA") (pintype "bidirectional"))
    )
    (net (code "25") (name "SENSORS") (class "Default")
      (node (ref "C17") (pin "1") (pinfunction "1_1") (pintype "passive"))
      (node (ref "IC3") (pin "8") (pinfunction "CH0_8") (pintype "input"))
      (node (ref "R6") (pin "2") (pinfunction "2_2") (pintype "passive"))
    )
    (net (code "26") (name "SOIL_MOISTURE_0") (class "Default")
      (node (ref "R13") (pin "1") (pinfunction "1_1") (pintype "passive"))
      (node (ref "R14") (pin "1") (pinfunction "1_1") (pintype "passive"))
      (node (ref "R15") (pin "2") (pinfunction "2_2") (pintype "passive"))
      (node (ref "X1") (pin "1") (pinfunction "S_1") (pintype "passive"))
    )
    (net (code "27") (name "SOIL_MOISTURE_1") (class "Default")
      (node (ref "R17") (pin "2") (pinfunction "2_2") (pintype "passive"))
      (node (ref "R18") (pin "1") (pinfunction "1_1") (pintype "passive"))
      (node (ref "R19") (pin "1") (pinfunction "1_1") (pintype "passive"))
      (node (ref "X1") (pin "3") (pinfunction "S_3") (pintype "passive"))
    )
    (net (code "28") (name "SOIL_MOISTURE_AMPLIFIED_0") (class "Default")
      (node (ref "IC5") (pin "13") (pinfunction "X0_13") (pintype "bidirectional"))
      (node (ref "IC6") (pin "1") (pinfunction "OUT_1") (pintype "output"))
      (node (ref "R12") (pin "2") (pinfunction "2_2") (pintype "passive"))
      (node (ref "R13") (pin "2") (pinfunction "2_2") (pintype "passive"))
    )
    (net (code "29") (name "SOIL_MOISTURE_AMPLIFIED_1") (class "Default")
      (node (ref "IC5") (pin "14") (pinfunction "X1_14") (pintype "bidirectional"))
      (node (ref "IC6") (pin "7") (pinfunction "OUT_7") (pintype "output"))
      (node (ref "R19") (pin "2") (pinfunction "2_2") (pintype "passive"))
      (node (ref "R20") (pin "2") (pinfunction "2_2") (pintype "passive"))
    )
    (net (code "30") (name "TX") (class "Default")
      (node (ref "IC1") (pin "19") (pinfunction "PB5(SCK)_19") (pintype "bidirectional"))
      (node (ref "U1") (pin "19") (pinfunction "TX_19") (pintype "bidirectional"))
    )
    (net (code "31") (name "unconnected-(IC1-AREF-Pad21)") (class "Default")
      (node (ref "IC1") (pin "21") (pinfunction "AREF_21") (pintype "passive"))
    )
    (net (code "32") (name "unconnected-(IC1-AVCC-Pad20)") (class "Default")
      (node (ref "IC1") (pin "20") (pinfunction "AVCC_20") (pintype "power_in"))
    )
    (net (code "33") (name "unconnected-(IC1-GND-Pad22)") (class "Default")
      (node (ref "IC1") (pin "22") (pinfunction "GND_22") (pintype "power_in"))
    )
    (net (code "34") (name "unconnected-(IC1-PB0(ICP)-Pad14)") (class "Default")
      (node (ref "IC1") (pin "14") (pinfunction "PB0(ICP)_14") (pintype "bidirectional"))
    )
    (net (code "35") (name "unconnected-(IC1-PB1(OC1A)-Pad15)") (class "Default")
      (node (ref "IC1") (pin "15") (pinfunction "PB1(OC1A)_15") (pintype "bidirectional"))
    )
    (net (code "36") (name "unconnected-(IC1-PB2(SS{slash}OC1B)-Pad16)") (class "Default")
      (node (ref "IC1") (pin "16") (pinfunction "PB2(SS/OC1B)_16") (pintype "bidirectional"))
    )
    (net (code "37") (name "unconnected-(IC1-PB3(MOSI{slash}OC2)-Pad17)") (class "Default")
      (node (ref "IC1") (pin "17") (pinfunction "PB3(MOSI/OC2)_17") (pintype "bidirectional"))
    )
    (net (code "38") (name "unconnected-(IC1-PC0(ADC0)-Pad23)") (class "Default")
      (node (ref "IC1") (pin "23") (pinfunction "PC0(ADC0)_23") (pintype "bidirectional"))
    )
    (net (code "39") (name "unconnected-(IC1-PC1(ADC1)-Pad24)") (class "Default")
      (node (ref "IC1") (pin "24") (pinfunction "PC1(ADC1)_24") (pintype "bidirectional"))
    )
    (net (code "40") (name "unconnected-(IC1-PC2(ADC2)-Pad25)") (class "Default")
      (node (ref "IC1") (pin "25") (pinfunction "PC2(ADC2)_25") (pintype "bidirectional"))
    )
    (net (code "41") (name "unconnected-(IC1-PC3(ADC3)-Pad26)") (class "Default")
      (node (ref "IC1") (pin "26") (pinfunction "PC3(ADC3)_26") (pintype "bidirectional"))
    )
    (net (code "42") (name "unconnected-(IC1-PD0(RXD)-Pad2)") (class "Default")
      (node (ref "IC1") (pin "2") (pinfunction "PD0(RXD)_2") (pintype "bidirectional"))
    )
    (net (code "43") (name "unconnected-(IC1-PD1(TXD)-Pad3)") (class "Default")
      (node (ref "IC1") (pin "3") (pinfunction "PD1(TXD)_3") (pintype "bidirectional"))
    )
    (net (code "44") (name "unconnected-(IC1-PD5(T1)-Pad11)") (class "Default")
      (node (ref "IC1") (pin "11") (pinfunction "PD5(T1)_11") (pintype "bidirectional"))
    )
    (net (code "45") (name "unconnected-(IC1-PD6(AIN0)-Pad12)") (class "Default")
      (node (ref "IC1") (pin "12") (pinfunction "PD6(AIN0)_12") (pintype "bidirectional"))
    )
    (net (code "46") (name "unconnected-(IC1-PD7(AIN1)-Pad13)") (class "Default")
      (node (ref "IC1") (pin "13") (pinfunction "PD7(AIN1)_13") (pintype "bidirectional"))
    )
    (net (code "47") (name "unconnected-(IC3-CH1-Pad9)") (class "Default")
      (node (ref "IC3") (pin "9") (pinfunction "CH1_9") (pintype "input"))
    )
    (net (code "48") (name "unconnected-(IC3-CH2-Pad10)") (class "Default")
      (node (ref "IC3") (pin "10") (pinfunction "CH2_10") (pintype "input"))
    )
    (net (code "49") (name "unconnected-(IC3-CH3-Pad11)") (class "Default")
      (node (ref "IC3") (pin "11") (pinfunction "CH3_11") (pintype "input"))
    )
    (net (code "50") (name "unconnected-(IC3-COM-Pad7)") (class "Default")
      (node (ref "IC3") (pin "7") (pinfunction "COM_7") (pintype "power_in"))
    )
    (net (code "51") (name "unconnected-(IC3-SDO-Pad5)") (class "Default")
      (node (ref "IC3") (pin "5") (pinfunction "SDO_5") (pintype "output"))
    )
    (net (code "52") (name "unconnected-(IC5A-X2-Pad15)") (class "Default")
      (node (ref "IC5") (pin "15") (pinfunction "X2_15") (pintype "bidirectional"))
    )
    (net (code "53") (name "unconnected-(IC5A-X3-Pad12)") (class "Default")
      (node (ref "IC5") (pin "12") (pinfunction "X3_12") (pintype "bidirectional"))
    )
    (net (code "54") (name "unconnected-(IC5A-X4-Pad1)") (class "Default")
      (node (ref "IC5") (pin "1") (pinfunction "X4_1") (pintype "bidirectional"))
    )
    (net (code "55") (name "unconnected-(IC5A-X5-Pad5)") (class "Default")
      (node (ref "IC5") (pin "5") (pinfunction "X5_5") (pintype "bidirectional"))
    )
    (net (code "56") (name "unconnected-(IC5A-X6-Pad2)") (class "Default")
      (node (ref "IC5") (pin "2") (pinfunction "X6_2") (pintype "bidirectional"))
    )
    (net (code "57") (name "unconnected-(IC5A-X7-Pad4)") (class "Default")
      (node (ref "IC5") (pin "4") (pinfunction "X7_4") (pintype "bidirectional"))
    )
    (net (code "58") (name "unconnected-(U1-DBG_CRF1-Pad28)") (class "Default")
      (node (ref "U1") (pin "28") (pinfunction "DBG_CRF1_28") (pintype "bidirectional"))
    )
    (net (code "59") (name "unconnected-(U1-DBG_CRF2-Pad30)") (class "Default")
      (node (ref "U1") (pin "30") (pinfunction "DBG_CRF2_30") (pintype "bidirectional"))
    )
    (net (code "60") (name "unconnected-(U1-DBG_CRF3-Pad29)") (class "Default")
      (node (ref "U1") (pin "29") (pinfunction "DBG_CRF3_29") (pintype "bidirectional"))
    )
    (net (code "61") (name "unconnected-(U1-DBG_SX1275_DIO3-Pad9)") (class "Default")
      (node (ref "U1") (pin "9") (pinfunction "DBG_SX1275_DIO3_9") (pintype "bidirectional"))
    )
    (net (code "62") (name "unconnected-(U1-DBG_SX1276_DIO0-Pad13)") (class "Default")
      (node (ref "U1") (pin "13") (pinfunction "DBG_SX1276_DIO0_13") (pintype "bidirectional"))
    )
    (net (code "63") (name "unconnected-(U1-DBG_SX1276_DIO1-Pad12)") (class "Default")
      (node (ref "U1") (pin "12") (pinfunction "DBG_SX1276_DIO1_12") (pintype "bidirectional"))
    )
    (net (code "64") (name "unconnected-(U1-DBG_SX1276_DIO2-Pad8)") (class "Default")
      (node (ref "U1") (pin "8") (pinfunction "DBG_SX1276_DIO2_8") (pintype "bidirectional"))
    )
    (net (code "65") (name "unconnected-(U1-DBG_SX1276_DIO5-Pad11)") (class "Default")
      (node (ref "U1") (pin "11") (pinfunction "DBG_SX1276_DIO5_11") (pintype "bidirectional"))
    )
    (net (code "66") (name "unconnected-(U1-GND-Pad3)") (class "Default")
      (node (ref "U1") (pin "3") (pinfunction "GND_3") (pintype "bidirectional"))
    )
    (net (code "67") (name "unconnected-(U1-PA0-Pad33)") (class "Default")
      (node (ref "U1") (pin "33") (pinfunction "PA0_33") (pintype "bidirectional"))
    )
    (net (code "68") (name "unconnected-(U1-PA2-Pad24)") (class "Default")
      (node (ref "U1") (pin "24") (pinfunction "PA2_24") (pintype "bidirectional"))
    )
    (net (code "69") (name "unconnected-(U1-PA3-Pad23)") (class "Default")
      (node (ref "U1") (pin "23") (pinfunction "PA3_23") (pintype "bidirectional"))
    )
    (net (code "70") (name "unconnected-(U1-PA4-Pad22)") (class "Default")
      (node (ref "U1") (pin "22") (pinfunction "PA4_22") (pintype "bidirectional"))
    )
    (net (code "71") (name "unconnected-(U1-PA5-Pad21)") (class "Default")
      (node (ref "U1") (pin "21") (pinfunction "PA5_21") (pintype "bidirectional"))
    )
    (net (code "72") (name "unconnected-(U1-PA8-Pad20)") (class "Default")
      (node (ref "U1") (pin "20") (pinfunction "PA8_20") (pintype "bidirectional"))
    )
    (net (code "73") (name "unconnected-(U1-PA11-Pad2)") (class "Default")
      (node (ref "U1") (pin "2") (pinfunction "PA11_2") (pintype "bidirectional"))
    )
    (net (code "74") (name "unconnected-(U1-PA12-Pad1)") (class "Default")
      (node (ref "U1") (pin "1") (pinfunction "PA12_1") (pintype "bidirectional"))
    )
    (net (code "75") (name "unconnected-(U1-PB2-Pad37)") (class "Default")
      (node (ref "U1") (pin "37") (pinfunction "PB2_37") (pintype "bidirectional"))
    )
    (net (code "76") (name "unconnected-(U1-PB5-Pad40)") (class "Default")
      (node (ref "U1") (pin "40") (pinfunction "PB5_40") (pintype "bidirectional"))
    )
    (net (code "77") (name "unconnected-(U1-PB6-Pad39)") (class "Default")
      (node (ref "U1") (pin "39") (pinfunction "PB6_39") (pintype "bidirectional"))
    )
    (net (code "78") (name "unconnected-(U1-PB7-Pad38)") (class "Default")
      (node (ref "U1") (pin "38") (pinfunction "PB7_38") (pintype "bidirectional"))
    )
    (net (code "79") (name "unconnected-(U1-PB8-Pad35)") (class "Default")
      (node (ref "U1") (pin "35") (pinfunction "PB8_35") (pintype "bidirectional"))
    )
    (net (code "80") (name "unconnected-(U1-PB9-Pad36)") (class "Default")
      (node (ref "U1") (pin "36") (pinfunction "PB9_36") (pintype "bidirectional"))
    )
    (net (code "81") (name "unconnected-(U1-PB12-Pad17)") (class "Default")
      (node (ref "U1") (pin "17") (pinfunction "PB12_17") (pintype "bidirectional"))
    )
    (net (code "82") (name "unconnected-(U1-PB13-Pad16)") (class "Default")
      (node (ref "U1") (pin "16") (pinfunction "PB13_16") (pintype "bidirectional"))
    )
    (net (code "83") (name "unconnected-(U1-PB14-Pad15)") (class "Default")
      (node (ref "U1") (pin "15") (pinfunction "PB14_15") (pintype "bidirectional"))
    )
    (net (code "84") (name "unconnected-(U1-PB15-Pad14)") (class "Default")
      (node (ref "U1") (pin "14") (pinfunction "PB15_14") (pintype "bidirectional"))
    )
    (net (code "85") (name "unconnected-(U1-PH0-OSC_IN-Pad46)") (class "Default")
      (node (ref "U1") (pin "46") (pinfunction "PH0-OSC_IN_46") (pintype "bidirectional"))
    )
    (net (code "86") (name "unconnected-(U1-PH1-OSC_OUT-Pad45)") (class "Default")
      (node (ref "U1") (pin "45") (pinfunction "PH1-OSC_OUT_45") (pintype "bidirectional"))
    )
    (net (code "87") (name "unconnected-(U1-STSAFE_NRST-Pad31)") (class "Default")
      (node (ref "U1") (pin "31") (pinfunction "STSAFE_NRST_31") (pintype "bidirectional"))
    )
    (net (code "88") (name "unconnected-(U1-SWCLK-Pad42)") (class "Default")
      (node (ref "U1") (pin "42") (pinfunction "SWCLK_42") (pintype "bidirectional"))
    )
    (net (code "89") (name "unconnected-(U1-SWDIO-Pad41)") (class "Default")
      (node (ref "U1") (pin "41") (pinfunction "SWDIO_41") (pintype "bidirectional"))
    )
    (net (code "90") (name "unconnected-(U1-SX1276_DIO4-Pad10)") (class "Default")
      (node (ref "U1") (pin "10") (pinfunction "SX1276_DIO4_10") (pintype "bidirectional"))
    )
    (net (code "91") (name "unconnected-(U1-TCXO_OUT-Pad47)") (class "Default")
      (node (ref "U1") (pin "47") (pinfunction "TCXO_OUT_47") (pintype "bidirectional"))
    )
    (net (code "92") (name "unconnected-(U1-VDD_TCXO-Pad48)") (class "Default")
      (node (ref "U1") (pin "48") (pinfunction "VDD_TCXO_48") (pintype "bidirectional"))
    )
    (net (code "93") (name "unconnected-(U1-VDD_USB-Pad4)") (class "Default")
      (node (ref "U1") (pin "4") (pinfunction "VDD_USB_4") (pintype "bidirectional"))
    )
  )
)
